# adapter.net
KiCad netlist of a schematic drawn in EAGLE
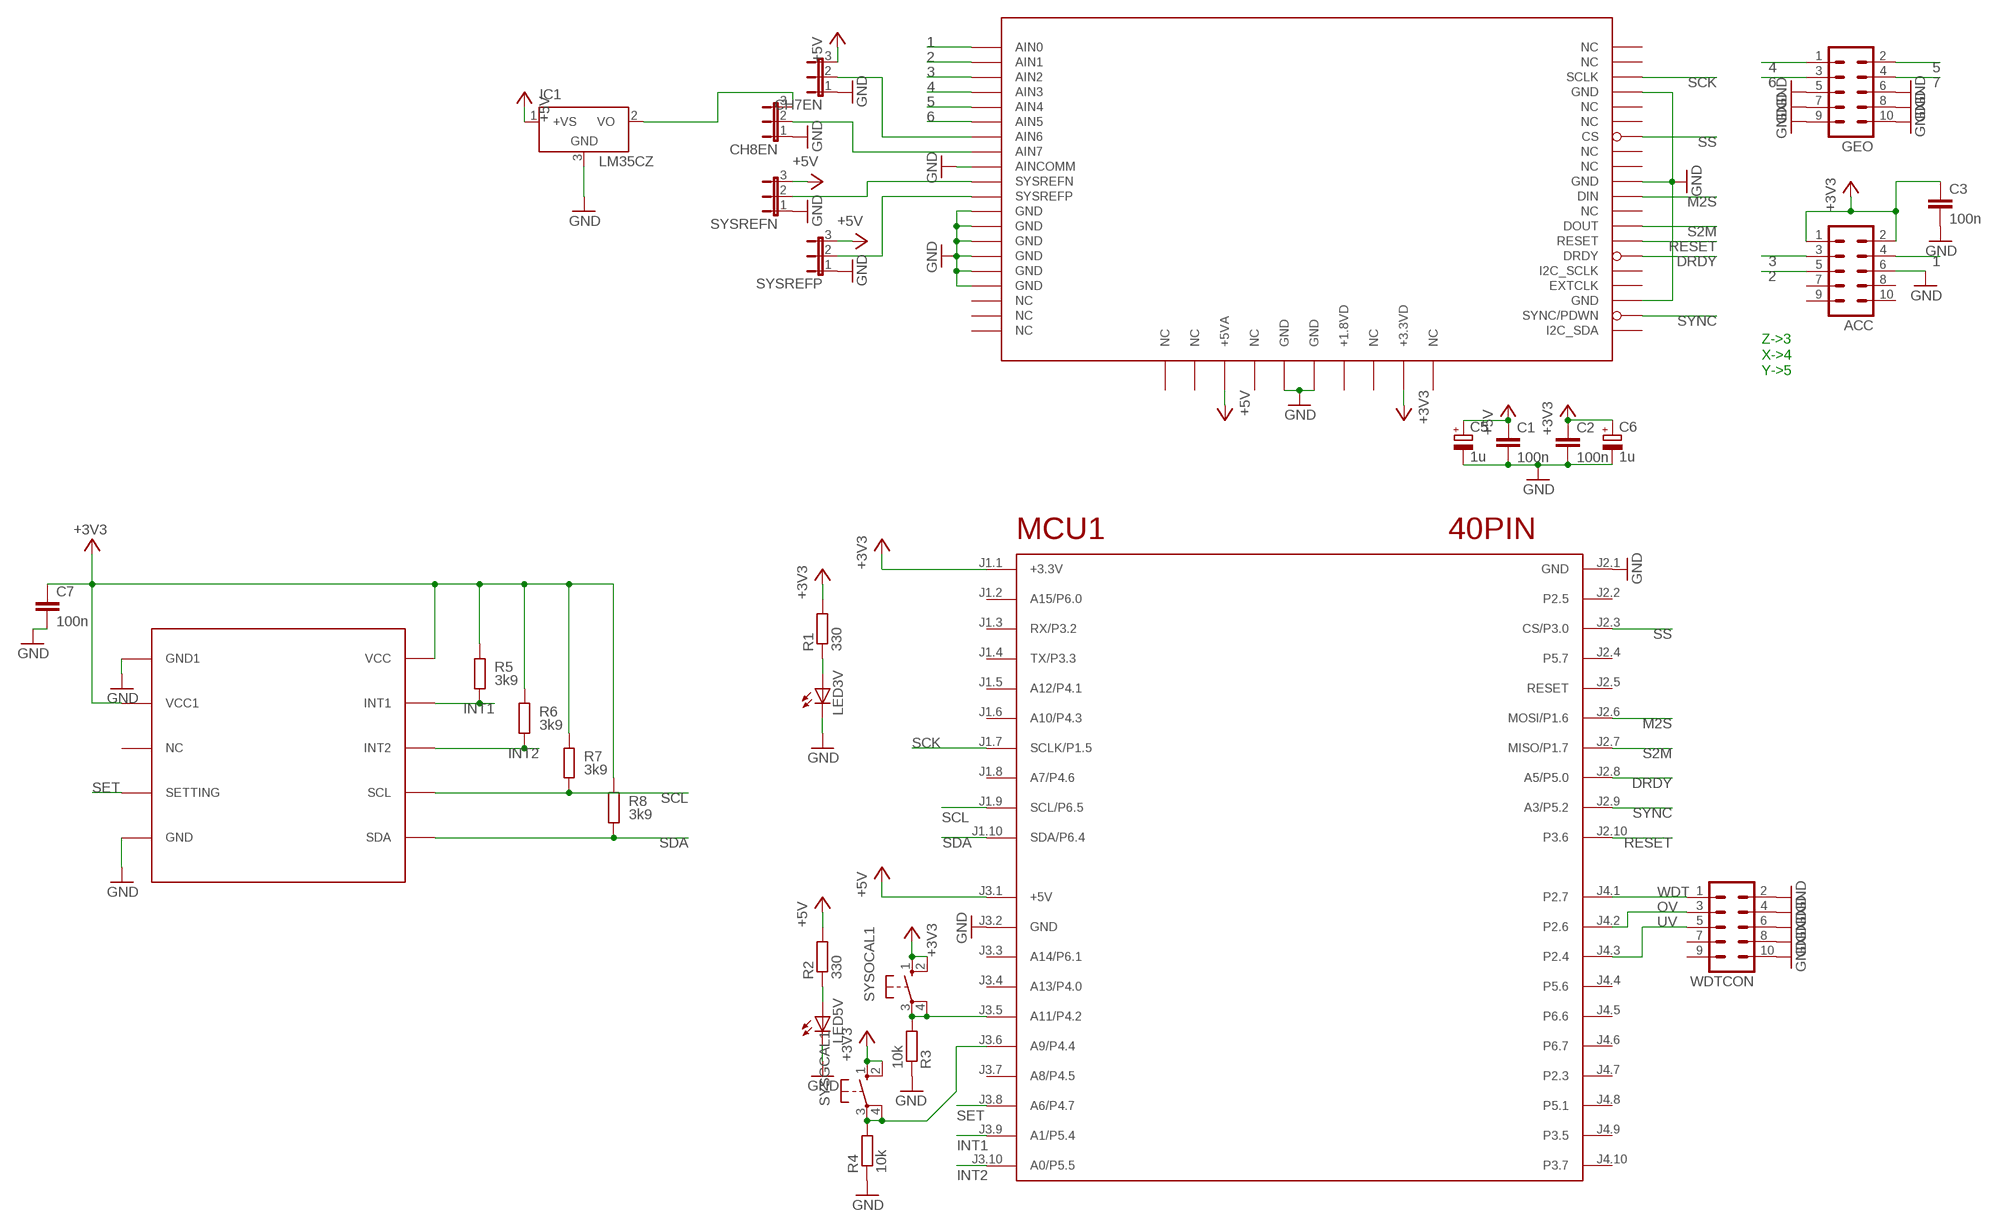
[diagram p0: schematic, sheet 1]

(export (version "E")
  (design (tool "Eeschema 10.0.6"))
  (components
    (comp (ref "ACC")
      (value "ML10")
      (footprint "eagle-import:ML10")
      (libsource (lib "eagle-import") (part "ML10"))
    )
    (comp (ref "C1")
      (value "100n")
      (footprint "eagle-import:C050-025X075")
      (libsource (lib "eagle-import") (part "C-EU050-025X075"))
    )
    (comp (ref "C2")
      (value "100n")
      (footprint "eagle-import:C050-025X075")
      (libsource (lib "eagle-import") (part "C-EU050-025X075"))
    )
    (comp (ref "C3")
      (value "100n")
      (footprint "eagle-import:C050-025X075")
      (libsource (lib "eagle-import") (part "C-EU050-025X075"))
    )
    (comp (ref "C5")
      (value "1u")
      (footprint "eagle-import:E2,5-6E")
      (libsource (lib "eagle-import") (part "CPOL-EUE2,5-6E"))
    )
    (comp (ref "C6")
      (value "1u")
      (footprint "eagle-import:E2,5-6E")
      (libsource (lib "eagle-import") (part "CPOL-EUE2,5-6E"))
    )
    (comp (ref "C7")
      (value "100n")
      (footprint "eagle-import:C050-025X075")
      (libsource (lib "eagle-import") (part "C-EU050-025X075"))
    )
    (comp (ref "CH7EN")
      (value "JP2E")
      (footprint "eagle-import:JP2")
      (libsource (lib "eagle-import") (part "JP2E"))
    )
    (comp (ref "CH8EN")
      (value "JP2E")
      (footprint "eagle-import:JP2")
      (libsource (lib "eagle-import") (part "JP2E"))
    )
    (comp (ref "GEO")
      (value "ML10")
      (footprint "eagle-import:ML10")
      (libsource (lib "eagle-import") (part "ML10"))
    )
    (comp (ref "IC1")
      (value "LM35CZ")
      (footprint "eagle-import:TO92")
      (libsource (lib "eagle-import") (part "LM35CZ"))
    )
    (comp (ref "LED3V")
      (value "LED3MM")
      (footprint "eagle-import:LED3MM")
      (libsource (lib "eagle-import") (part "LED3MM"))
    )
    (comp (ref "LED5V")
      (value "LED3MM")
      (footprint "eagle-import:LED3MM")
      (libsource (lib "eagle-import") (part "LED3MM"))
    )
    (comp (ref "MCU1")
      (value "40PIN")
      (footprint "eagle-import:40PIN")
      (libsource (lib "eagle-import") (part "40PIN"))
    )
    (comp (ref "R1")
      (value "330")
      (footprint "eagle-import:0207_10")
      (libsource (lib "eagle-import") (part "R-EU_0207/10"))
    )
    (comp (ref "R2")
      (value "330")
      (footprint "eagle-import:0207_10")
      (libsource (lib "eagle-import") (part "R-EU_0207/10"))
    )
    (comp (ref "R3")
      (value "10k")
      (footprint "eagle-import:0207_10")
      (libsource (lib "eagle-import") (part "R-EU_0207/10"))
    )
    (comp (ref "R4")
      (value "10k")
      (footprint "eagle-import:0207_10")
      (libsource (lib "eagle-import") (part "R-EU_0207/10"))
    )
    (comp (ref "R5")
      (value "3k9")
      (footprint "eagle-import:0207_10")
      (fields (field (name "TOLERANCE") "5%"))
      (libsource (lib "eagle-import") (part "resistor_R-EU_0207/10"))
    )
    (comp (ref "R6")
      (value "3k9")
      (footprint "eagle-import:0207_10")
      (fields (field (name "TOLERANCE") "5%"))
      (libsource (lib "eagle-import") (part "resistor_R-EU_0207/10"))
    )
    (comp (ref "R7")
      (value "3k9")
      (footprint "eagle-import:0207_10")
      (fields (field (name "TOLERANCE") "5%"))
      (libsource (lib "eagle-import") (part "resistor_R-EU_0207/10"))
    )
    (comp (ref "R8")
      (value "3k9")
      (footprint "eagle-import:0207_10")
      (fields (field (name "TOLERANCE") "5%"))
      (libsource (lib "eagle-import") (part "resistor_R-EU_0207/10"))
    )
    (comp (ref "SYSGCAL1")
      (value "10-XX")
      (footprint "eagle-import:B3F-10XX")
      (fields (field (name "MPN") "B3F-1000"))
      (libsource (lib "eagle-import") (part "10-XX"))
    )
    (comp (ref "SYSOCAL1")
      (value "10-XX")
      (footprint "eagle-import:B3F-10XX")
      (fields (field (name "MPN") "B3F-1000"))
      (libsource (lib "eagle-import") (part "10-XX"))
    )
    (comp (ref "SYSREFN")
      (value "JP2E")
      (footprint "eagle-import:JP2")
      (libsource (lib "eagle-import") (part "JP2E"))
    )
    (comp (ref "SYSREFP")
      (value "JP2E")
      (footprint "eagle-import:JP2")
      (libsource (lib "eagle-import") (part "JP2E"))
    )
    (comp (ref "U$1")
      (value "D7S")
      (footprint "eagle-import:D7S")
      (libsource (lib "eagle-import") (part "D7S"))
    )
    (comp (ref "U$2")
      (value "ADS1256EVM")
      (footprint "eagle-import:ADS1256EVM")
      (libsource (lib "eagle-import") (part "ADS1256EVM"))
    )
    (comp (ref "WDTCON")
      (value "ML10")
      (footprint "eagle-import:ML10")
      (libsource (lib "eagle-import") (part "ML10"))
    )
  )
  (nets
    (net (code "1") (name "+3V3") (class "Default")
      (node (ref "ACC") (pin "1") (pinfunction "1_1") (pintype "passive"))
      (node (ref "ACC") (pin "2") (pinfunction "2_2") (pintype "passive"))
      (node (ref "C2") (pin "1") (pinfunction "1_1") (pintype "passive"))
      (node (ref "C3") (pin "1") (pinfunction "1_1") (pintype "passive"))
      (node (ref "C6") (pin "+") (pinfunction "+_+") (pintype "passive"))
      (node (ref "C7") (pin "1") (pinfunction "1_1") (pintype "passive"))
      (node (ref "MCU1") (pin "J1.1") (pinfunction "+3.3V_J1.1") (pintype "bidirectional"))
      (node (ref "R1") (pin "2") (pinfunction "2_2") (pintype "passive"))
      (node (ref "R5") (pin "2") (pinfunction "2_2") (pintype "passive"))
      (node (ref "R6") (pin "2") (pinfunction "2_2") (pintype "passive"))
      (node (ref "R7") (pin "2") (pinfunction "2_2") (pintype "passive"))
      (node (ref "R8") (pin "2") (pinfunction "2_2") (pintype "passive"))
      (node (ref "SYSGCAL1") (pin "1") (pinfunction "S_1") (pintype "passive"))
      (node (ref "SYSGCAL1") (pin "2") (pinfunction "S1_2") (pintype "passive"))
      (node (ref "SYSOCAL1") (pin "1") (pinfunction "S_1") (pintype "passive"))
      (node (ref "SYSOCAL1") (pin "2") (pinfunction "S1_2") (pintype "passive"))
      (node (ref "U$1") (pin "P$1") (pinfunction "VCC_P$1") (pintype "bidirectional"))
      (node (ref "U$1") (pin "P$9") (pinfunction "VCC1_P$9") (pintype "bidirectional"))
      (node (ref "U$2") (pin "J3.9") (pinfunction "+3.3VD_J3.9") (pintype "bidirectional"))
    )
    (net (code "2") (name "+5V") (class "Default")
      (node (ref "C1") (pin "1") (pinfunction "1_1") (pintype "passive"))
      (node (ref "C5") (pin "+") (pinfunction "+_+") (pintype "passive"))
      (node (ref "CH7EN") (pin "3") (pinfunction "3_3") (pintype "passive"))
      (node (ref "IC1") (pin "1") (pinfunction "+VS_1") (pintype "input"))
      (node (ref "MCU1") (pin "J3.1") (pinfunction "+5V_J3.1") (pintype "bidirectional"))
      (node (ref "R2") (pin "2") (pinfunction "2_2") (pintype "passive"))
      (node (ref "SYSREFN") (pin "3") (pinfunction "3_3") (pintype "passive"))
      (node (ref "SYSREFP") (pin "3") (pinfunction "3_3") (pintype "passive"))
      (node (ref "U$2") (pin "J3.3") (pinfunction "+5VA_J3.3") (pintype "bidirectional"))
    )
    (net (code "3") (name "/1") (class "Default")
      (node (ref "ACC") (pin "4") (pinfunction "4_4") (pintype "passive"))
      (node (ref "U$2") (pin "J1.1") (pinfunction "AIN0_J1.1") (pintype "bidirectional"))
    )
    (net (code "4") (name "/2") (class "Default")
      (node (ref "ACC") (pin "5") (pinfunction "5_5") (pintype "passive"))
      (node (ref "U$2") (pin "J1.2") (pinfunction "AIN1_J1.2") (pintype "bidirectional"))
    )
    (net (code "5") (name "/3") (class "Default")
      (node (ref "ACC") (pin "3") (pinfunction "3_3") (pintype "passive"))
      (node (ref "U$2") (pin "J1.3") (pinfunction "AIN2_J1.3") (pintype "bidirectional"))
    )
    (net (code "6") (name "/4") (class "Default")
      (node (ref "GEO") (pin "1") (pinfunction "1_1") (pintype "passive"))
      (node (ref "U$2") (pin "J1.4") (pinfunction "AIN3_J1.4") (pintype "bidirectional"))
    )
    (net (code "7") (name "/5") (class "Default")
      (node (ref "GEO") (pin "2") (pinfunction "2_2") (pintype "passive"))
      (node (ref "U$2") (pin "J1.5") (pinfunction "AIN4_J1.5") (pintype "bidirectional"))
    )
    (net (code "8") (name "/6") (class "Default")
      (node (ref "GEO") (pin "3") (pinfunction "3_3") (pintype "passive"))
      (node (ref "U$2") (pin "J1.6") (pinfunction "AIN5_J1.6") (pintype "bidirectional"))
    )
    (net (code "9") (name "/7") (class "Default")
      (node (ref "GEO") (pin "4") (pinfunction "4_4") (pintype "passive"))
    )
    (net (code "10") (name "/DRDY") (class "Default")
      (node (ref "MCU1") (pin "J2.8") (pinfunction "A5/P5.0_J2.8") (pintype "bidirectional"))
      (node (ref "U$2") (pin "J2.15") (pinfunction "DRDY_J2.15") (pintype "bidirectional"))
    )
    (net (code "11") (name "/INT1") (class "Default")
      (node (ref "MCU1") (pin "J3.9") (pinfunction "A1/P5.4_J3.9") (pintype "bidirectional"))
      (node (ref "R5") (pin "1") (pinfunction "1_1") (pintype "passive"))
      (node (ref "U$1") (pin "P$2") (pinfunction "INT1_P$2") (pintype "bidirectional"))
    )
    (net (code "12") (name "/INT2") (class "Default")
      (node (ref "MCU1") (pin "J3.10") (pinfunction "A0/P5.5_J3.10") (pintype "bidirectional"))
      (node (ref "R6") (pin "1") (pinfunction "1_1") (pintype "passive"))
      (node (ref "U$1") (pin "P$3") (pinfunction "INT2_P$3") (pintype "bidirectional"))
    )
    (net (code "13") (name "/M2S") (class "Default")
      (node (ref "MCU1") (pin "J2.6") (pinfunction "MOSI/P1.6_J2.6") (pintype "bidirectional"))
      (node (ref "U$2") (pin "J2.11") (pinfunction "DIN_J2.11") (pintype "bidirectional"))
    )
    (net (code "14") (name "/OV") (class "Default")
      (node (ref "MCU1") (pin "J4.2") (pinfunction "P2.6_J4.2") (pintype "bidirectional"))
      (node (ref "WDTCON") (pin "3") (pinfunction "3_3") (pintype "passive"))
    )
    (net (code "15") (name "/RESET") (class "Default")
      (node (ref "MCU1") (pin "J2.10") (pinfunction "P3.6_J2.10") (pintype "bidirectional"))
      (node (ref "U$2") (pin "J2.14") (pinfunction "RESET_J2.14") (pintype "bidirectional"))
    )
    (net (code "16") (name "/S2M") (class "Default")
      (node (ref "MCU1") (pin "J2.7") (pinfunction "MISO/P1.7_J2.7") (pintype "bidirectional"))
      (node (ref "U$2") (pin "J2.13") (pinfunction "DOUT_J2.13") (pintype "bidirectional"))
    )
    (net (code "17") (name "/SCK") (class "Default")
      (node (ref "MCU1") (pin "J1.7") (pinfunction "SCLK/P1.5_J1.7") (pintype "bidirectional"))
      (node (ref "U$2") (pin "J2.3") (pinfunction "SCLK_J2.3") (pintype "bidirectional"))
    )
    (net (code "18") (name "/SCL") (class "Default")
      (node (ref "MCU1") (pin "J1.9") (pinfunction "SCL/P6.5_J1.9") (pintype "bidirectional"))
      (node (ref "R7") (pin "1") (pinfunction "1_1") (pintype "passive"))
      (node (ref "U$1") (pin "P$4") (pinfunction "SCL_P$4") (pintype "bidirectional"))
    )
    (net (code "19") (name "/SDA") (class "Default")
      (node (ref "MCU1") (pin "J1.10") (pinfunction "SDA/P6.4_J1.10") (pintype "bidirectional"))
      (node (ref "R8") (pin "1") (pinfunction "1_1") (pintype "passive"))
      (node (ref "U$1") (pin "P$5") (pinfunction "SDA_P$5") (pintype "bidirectional"))
    )
    (net (code "20") (name "/SET") (class "Default")
      (node (ref "MCU1") (pin "J3.8") (pinfunction "A6/P4.7_J3.8") (pintype "bidirectional"))
      (node (ref "U$1") (pin "P$7") (pinfunction "SETTING_P$7") (pintype "bidirectional"))
    )
    (net (code "21") (name "/SS") (class "Default")
      (node (ref "MCU1") (pin "J2.3") (pinfunction "CS/P3.0_J2.3") (pintype "bidirectional"))
      (node (ref "U$2") (pin "J2.7") (pinfunction "CS_J2.7") (pintype "bidirectional"))
    )
    (net (code "22") (name "/SYNC") (class "Default")
      (node (ref "MCU1") (pin "J2.9") (pinfunction "A3/P5.2_J2.9") (pintype "bidirectional"))
      (node (ref "U$2") (pin "J2.19") (pinfunction "SYNC/PDWN_J2.19") (pintype "bidirectional"))
    )
    (net (code "23") (name "/UV") (class "Default")
      (node (ref "MCU1") (pin "J4.3") (pinfunction "P2.4_J4.3") (pintype "bidirectional"))
      (node (ref "WDTCON") (pin "5") (pinfunction "5_5") (pintype "passive"))
    )
    (net (code "24") (name "/WDT") (class "Default")
      (node (ref "MCU1") (pin "J4.1") (pinfunction "P2.7_J4.1") (pintype "bidirectional"))
      (node (ref "WDTCON") (pin "1") (pinfunction "1_1") (pintype "passive"))
    )
    (net (code "25") (name "GND") (class "Default")
      (node (ref "ACC") (pin "6") (pinfunction "6_6") (pintype "passive"))
      (node (ref "C1") (pin "2") (pinfunction "2_2") (pintype "passive"))
      (node (ref "C2") (pin "2") (pinfunction "2_2") (pintype "passive"))
      (node (ref "C3") (pin "2") (pinfunction "2_2") (pintype "passive"))
      (node (ref "C5") (pin "-") (pinfunction "-_-") (pintype "passive"))
      (node (ref "C6") (pin "-") (pinfunction "-_-") (pintype "passive"))
      (node (ref "C7") (pin "2") (pinfunction "2_2") (pintype "passive"))
      (node (ref "CH7EN") (pin "1") (pinfunction "1_1") (pintype "passive"))
      (node (ref "CH8EN") (pin "1") (pinfunction "1_1") (pintype "passive"))
      (node (ref "GEO") (pin "10") (pinfunction "10_10") (pintype "passive"))
      (node (ref "GEO") (pin "5") (pinfunction "5_5") (pintype "passive"))
      (node (ref "GEO") (pin "6") (pinfunction "6_6") (pintype "passive"))
      (node (ref "GEO") (pin "7") (pinfunction "7_7") (pintype "passive"))
      (node (ref "GEO") (pin "8") (pinfunction "8_8") (pintype "passive"))
      (node (ref "GEO") (pin "9") (pinfunction "9_9") (pintype "passive"))
      (node (ref "IC1") (pin "3") (pinfunction "GND_3") (pintype "power_in"))
      (node (ref "LED3V") (pin "K") (pinfunction "C_K") (pintype "passive"))
      (node (ref "LED5V") (pin "K") (pinfunction "C_K") (pintype "passive"))
      (node (ref "MCU1") (pin "J2.1") (pinfunction "GND_J2.1") (pintype "bidirectional"))
      (node (ref "MCU1") (pin "J3.2") (pinfunction "GND_J3.2") (pintype "bidirectional"))
      (node (ref "R3") (pin "1") (pinfunction "1_1") (pintype "passive"))
      (node (ref "R4") (pin "1") (pinfunction "1_1") (pintype "passive"))
      (node (ref "SYSREFN") (pin "1") (pinfunction "1_1") (pintype "passive"))
      (node (ref "SYSREFP") (pin "1") (pinfunction "1_1") (pintype "passive"))
      (node (ref "U$1") (pin "P$10") (pinfunction "GND1_P$10") (pintype "bidirectional"))
      (node (ref "U$1") (pin "P$6") (pinfunction "GND_P$6") (pintype "bidirectional"))
      (node (ref "U$2") (pin "J1.10") (pinfunction "AINCOMM_J1.10") (pintype "bidirectional"))
      (node (ref "U$2") (pin "J1.11") (pinfunction "GND_J1.11") (pintype "bidirectional"))
      (node (ref "U$2") (pin "J1.13") (pinfunction "GND_J1.13") (pintype "bidirectional"))
      (node (ref "U$2") (pin "J1.15") (pinfunction "GND_J1.15") (pintype "bidirectional"))
      (node (ref "U$2") (pin "J1.17") (pinfunction "GND_J1.17") (pintype "bidirectional"))
      (node (ref "U$2") (pin "J1.19") (pinfunction "GND_J1.19") (pintype "bidirectional"))
      (node (ref "U$2") (pin "J1.9") (pinfunction "GND_J1.9") (pintype "bidirectional"))
      (node (ref "U$2") (pin "J2.10") (pinfunction "GND_J2.10") (pintype "bidirectional"))
      (node (ref "U$2") (pin "J2.18") (pinfunction "GND_J2.18") (pintype "bidirectional"))
      (node (ref "U$2") (pin "J2.4") (pinfunction "GND_J2.4") (pintype "bidirectional"))
      (node (ref "U$2") (pin "J3.5") (pinfunction "GND_J3.5") (pintype "bidirectional"))
      (node (ref "U$2") (pin "J3.6") (pinfunction "GND_J3.6") (pintype "bidirectional"))
      (node (ref "WDTCON") (pin "10") (pinfunction "10_10") (pintype "passive"))
      (node (ref "WDTCON") (pin "2") (pinfunction "2_2") (pintype "passive"))
      (node (ref "WDTCON") (pin "4") (pinfunction "4_4") (pintype "passive"))
      (node (ref "WDTCON") (pin "6") (pinfunction "6_6") (pintype "passive"))
      (node (ref "WDTCON") (pin "8") (pinfunction "8_8") (pintype "passive"))
    )
    (net (code "26") (name "Net-(IC1-VO)") (class "Default")
      (node (ref "CH8EN") (pin "3") (pinfunction "3_3") (pintype "passive"))
      (node (ref "IC1") (pin "2") (pinfunction "VO_2") (pintype "input"))
    )
    (net (code "27") (name "Net-(LED3V-PadA)") (class "Default")
      (node (ref "LED3V") (pin "A") (pinfunction "A_A") (pintype "passive"))
      (node (ref "R1") (pin "1") (pinfunction "1_1") (pintype "passive"))
    )
    (net (code "28") (name "Net-(LED5V-PadA)") (class "Default")
      (node (ref "LED5V") (pin "A") (pinfunction "A_A") (pintype "passive"))
      (node (ref "R2") (pin "1") (pinfunction "1_1") (pintype "passive"))
    )
    (net (code "29") (name "Net-(MCU1-A9{slash}P4.4)") (class "Default")
      (node (ref "MCU1") (pin "J3.6") (pinfunction "A9/P4.4_J3.6") (pintype "bidirectional"))
      (node (ref "R4") (pin "2") (pinfunction "2_2") (pintype "passive"))
      (node (ref "SYSGCAL1") (pin "3") (pinfunction "P_3") (pintype "passive"))
      (node (ref "SYSGCAL1") (pin "4") (pinfunction "P1_4") (pintype "passive"))
    )
    (net (code "30") (name "Net-(MCU1-A11{slash}P4.2)") (class "Default")
      (node (ref "MCU1") (pin "J3.5") (pinfunction "A11/P4.2_J3.5") (pintype "bidirectional"))
      (node (ref "R3") (pin "2") (pinfunction "2_2") (pintype "passive"))
      (node (ref "SYSOCAL1") (pin "3") (pinfunction "P_3") (pintype "passive"))
      (node (ref "SYSOCAL1") (pin "4") (pinfunction "P1_4") (pintype "passive"))
    )
    (net (code "31") (name "Net-(U$2-AIN6)") (class "Default")
      (node (ref "CH7EN") (pin "2") (pinfunction "2_2") (pintype "passive"))
      (node (ref "U$2") (pin "J1.7") (pinfunction "AIN6_J1.7") (pintype "bidirectional"))
    )
    (net (code "32") (name "Net-(U$2-AIN7)") (class "Default")
      (node (ref "CH8EN") (pin "2") (pinfunction "2_2") (pintype "passive"))
      (node (ref "U$2") (pin "J1.8") (pinfunction "AIN7_J1.8") (pintype "bidirectional"))
    )
    (net (code "33") (name "Net-(U$2-SYSREFN)") (class "Default")
      (node (ref "SYSREFN") (pin "2") (pinfunction "2_2") (pintype "passive"))
      (node (ref "U$2") (pin "J1.18") (pinfunction "SYSREFN_J1.18") (pintype "bidirectional"))
    )
    (net (code "34") (name "Net-(U$2-SYSREFP)") (class "Default")
      (node (ref "SYSREFP") (pin "2") (pinfunction "2_2") (pintype "passive"))
      (node (ref "U$2") (pin "J1.20") (pinfunction "SYSREFP_J1.20") (pintype "bidirectional"))
    )
    (net (code "35") (name "unconnected-(ACC-Pad7)") (class "Default")
      (node (ref "ACC") (pin "7") (pinfunction "7_7") (pintype "passive"))
    )
    (net (code "36") (name "unconnected-(ACC-Pad8)") (class "Default")
      (node (ref "ACC") (pin "8") (pinfunction "8_8") (pintype "passive"))
    )
    (net (code "37") (name "unconnected-(ACC-Pad9)") (class "Default")
      (node (ref "ACC") (pin "9") (pinfunction "9_9") (pintype "passive"))
    )
    (net (code "38") (name "unconnected-(ACC-Pad10)") (class "Default")
      (node (ref "ACC") (pin "10") (pinfunction "10_10") (pintype "passive"))
    )
    (net (code "39") (name "unconnected-(MCU1-A7{slash}P4.6-PadJ1.8)") (class "Default")
      (node (ref "MCU1") (pin "J1.8") (pinfunction "A7/P4.6_J1.8") (pintype "bidirectional"))
    )
    (net (code "40") (name "unconnected-(MCU1-A8{slash}P4.5-PadJ3.7)") (class "Default")
      (node (ref "MCU1") (pin "J3.7") (pinfunction "A8/P4.5_J3.7") (pintype "bidirectional"))
    )
    (net (code "41") (name "unconnected-(MCU1-A10{slash}P4.3-PadJ1.6)") (class "Default")
      (node (ref "MCU1") (pin "J1.6") (pinfunction "A10/P4.3_J1.6") (pintype "bidirectional"))
    )
    (net (code "42") (name "unconnected-(MCU1-A12{slash}P4.1-PadJ1.5)") (class "Default")
      (node (ref "MCU1") (pin "J1.5") (pinfunction "A12/P4.1_J1.5") (pintype "bidirectional"))
    )
    (net (code "43") (name "unconnected-(MCU1-A13{slash}P4.0-PadJ3.4)") (class "Default")
      (node (ref "MCU1") (pin "J3.4") (pinfunction "A13/P4.0_J3.4") (pintype "bidirectional"))
    )
    (net (code "44") (name "unconnected-(MCU1-A14{slash}P6.1-PadJ3.3)") (class "Default")
      (node (ref "MCU1") (pin "J3.3") (pinfunction "A14/P6.1_J3.3") (pintype "bidirectional"))
    )
    (net (code "45") (name "unconnected-(MCU1-A15{slash}P6.0-PadJ1.2)") (class "Default")
      (node (ref "MCU1") (pin "J1.2") (pinfunction "A15/P6.0_J1.2") (pintype "bidirectional"))
    )
    (net (code "46") (name "unconnected-(MCU1-P2.3-PadJ4.7)") (class "Default")
      (node (ref "MCU1") (pin "J4.7") (pinfunction "P2.3_J4.7") (pintype "bidirectional"))
    )
    (net (code "47") (name "unconnected-(MCU1-P2.5-PadJ2.2)") (class "Default")
      (node (ref "MCU1") (pin "J2.2") (pinfunction "P2.5_J2.2") (pintype "bidirectional"))
    )
    (net (code "48") (name "unconnected-(MCU1-P3.5-PadJ4.9)") (class "Default")
      (node (ref "MCU1") (pin "J4.9") (pinfunction "P3.5_J4.9") (pintype "bidirectional"))
    )
    (net (code "49") (name "unconnected-(MCU1-P3.7-PadJ4.10)") (class "Default")
      (node (ref "MCU1") (pin "J4.10") (pinfunction "P3.7_J4.10") (pintype "bidirectional"))
    )
    (net (code "50") (name "unconnected-(MCU1-P5.1-PadJ4.8)") (class "Default")
      (node (ref "MCU1") (pin "J4.8") (pinfunction "P5.1_J4.8") (pintype "bidirectional"))
    )
    (net (code "51") (name "unconnected-(MCU1-P5.6-PadJ4.4)") (class "Default")
      (node (ref "MCU1") (pin "J4.4") (pinfunction "P5.6_J4.4") (pintype "bidirectional"))
    )
    (net (code "52") (name "unconnected-(MCU1-P5.7-PadJ2.4)") (class "Default")
      (node (ref "MCU1") (pin "J2.4") (pinfunction "P5.7_J2.4") (pintype "bidirectional"))
    )
    (net (code "53") (name "unconnected-(MCU1-P6.6-PadJ4.5)") (class "Default")
      (node (ref "MCU1") (pin "J4.5") (pinfunction "P6.6_J4.5") (pintype "bidirectional"))
    )
    (net (code "54") (name "unconnected-(MCU1-P6.7-PadJ4.6)") (class "Default")
      (node (ref "MCU1") (pin "J4.6") (pinfunction "P6.7_J4.6") (pintype "bidirectional"))
    )
    (net (code "55") (name "unconnected-(MCU1-RESET-PadJ2.5)") (class "Default")
      (node (ref "MCU1") (pin "J2.5") (pinfunction "RESET_J2.5") (pintype "bidirectional"))
    )
    (net (code "56") (name "unconnected-(MCU1-RX{slash}P3.2-PadJ1.3)") (class "Default")
      (node (ref "MCU1") (pin "J1.3") (pinfunction "RX/P3.2_J1.3") (pintype "bidirectional"))
    )
    (net (code "57") (name "unconnected-(MCU1-TX{slash}P3.3-PadJ1.4)") (class "Default")
      (node (ref "MCU1") (pin "J1.4") (pinfunction "TX/P3.3_J1.4") (pintype "bidirectional"))
    )
    (net (code "58") (name "unconnected-(U$1-NC-PadP$8)") (class "Default")
      (node (ref "U$1") (pin "P$8") (pinfunction "NC_P$8") (pintype "bidirectional"))
    )
    (net (code "59") (name "unconnected-(U$2-+1.8VD-PadJ3.7)") (class "Default")
      (node (ref "U$2") (pin "J3.7") (pinfunction "+1.8VD_J3.7") (pintype "bidirectional"))
    )
    (net (code "60") (name "unconnected-(U$2-EXTCLK-PadJ2.17)") (class "Default")
      (node (ref "U$2") (pin "J2.17") (pinfunction "EXTCLK_J2.17") (pintype "bidirectional"))
    )
    (net (code "61") (name "unconnected-(U$2-I2C_SCLK-PadJ2.16)") (class "Default")
      (node (ref "U$2") (pin "J2.16") (pinfunction "I2C_SCLK_J2.16") (pintype "bidirectional"))
    )
    (net (code "62") (name "unconnected-(U$2-I2C_SDA-PadJ2.20)") (class "Default")
      (node (ref "U$2") (pin "J2.20") (pinfunction "I2C_SDA_J2.20") (pintype "bidirectional"))
    )
    (net (code "63") (name "unconnected-(U$2-NC-PadJ1.12)") (class "Default")
      (node (ref "U$2") (pin "J1.12") (pinfunction "NC_J1.12") (pintype "bidirectional"))
    )
    (net (code "64") (name "unconnected-(U$2-NC-PadJ1.14)") (class "Default")
      (node (ref "U$2") (pin "J1.14") (pinfunction "NC_J1.14") (pintype "bidirectional"))
    )
    (net (code "65") (name "unconnected-(U$2-NC-PadJ1.16)") (class "Default")
      (node (ref "U$2") (pin "J1.16") (pinfunction "NC_J1.16") (pintype "bidirectional"))
    )
    (net (code "66") (name "unconnected-(U$2-NC-PadJ2.1)") (class "Default")
      (node (ref "U$2") (pin "J2.1") (pinfunction "NC_J2.1") (pintype "bidirectional"))
    )
    (net (code "67") (name "unconnected-(U$2-NC-PadJ2.2)") (class "Default")
      (node (ref "U$2") (pin "J2.2") (pinfunction "NC_J2.2") (pintype "bidirectional"))
    )
    (net (code "68") (name "unconnected-(U$2-NC-PadJ2.5)") (class "Default")
      (node (ref "U$2") (pin "J2.5") (pinfunction "NC_J2.5") (pintype "bidirectional"))
    )
    (net (code "69") (name "unconnected-(U$2-NC-PadJ2.6)") (class "Default")
      (node (ref "U$2") (pin "J2.6") (pinfunction "NC_J2.6") (pintype "bidirectional"))
    )
    (net (code "70") (name "unconnected-(U$2-NC-PadJ2.8)") (class "Default")
      (node (ref "U$2") (pin "J2.8") (pinfunction "NC_J2.8") (pintype "bidirectional"))
    )
    (net (code "71") (name "unconnected-(U$2-NC-PadJ2.9)") (class "Default")
      (node (ref "U$2") (pin "J2.9") (pinfunction "NC_J2.9") (pintype "bidirectional"))
    )
    (net (code "72") (name "unconnected-(U$2-NC-PadJ2.12)") (class "Default")
      (node (ref "U$2") (pin "J2.12") (pinfunction "NC_J2.12") (pintype "bidirectional"))
    )
    (net (code "73") (name "unconnected-(U$2-NC-PadJ3.1)") (class "Default")
      (node (ref "U$2") (pin "J3.1") (pinfunction "NC_J3.1") (pintype "bidirectional"))
    )
    (net (code "74") (name "unconnected-(U$2-NC-PadJ3.2)") (class "Default")
      (node (ref "U$2") (pin "J3.2") (pinfunction "NC_J3.2") (pintype "bidirectional"))
    )
    (net (code "75") (name "unconnected-(U$2-NC-PadJ3.4)") (class "Default")
      (node (ref "U$2") (pin "J3.4") (pinfunction "NC_J3.4") (pintype "bidirectional"))
    )
    (net (code "76") (name "unconnected-(U$2-NC-PadJ3.8)") (class "Default")
      (node (ref "U$2") (pin "J3.8") (pinfunction "NC_J3.8") (pintype "bidirectional"))
    )
    (net (code "77") (name "unconnected-(U$2-NC-PadJ3.10)") (class "Default")
      (node (ref "U$2") (pin "J3.10") (pinfunction "NC_J3.10") (pintype "bidirectional"))
    )
    (net (code "78") (name "unconnected-(WDTCON-Pad7)") (class "Default")
      (node (ref "WDTCON") (pin "7") (pinfunction "7_7") (pintype "passive"))
    )
    (net (code "79") (name "unconnected-(WDTCON-Pad9)") (class "Default")
      (node (ref "WDTCON") (pin "9") (pinfunction "9_9") (pintype "passive"))
    )
  )
)
